# Adafruit_MagTag_2_9in_Rev_C1.net
KiCad netlist of a schematic drawn in EAGLE
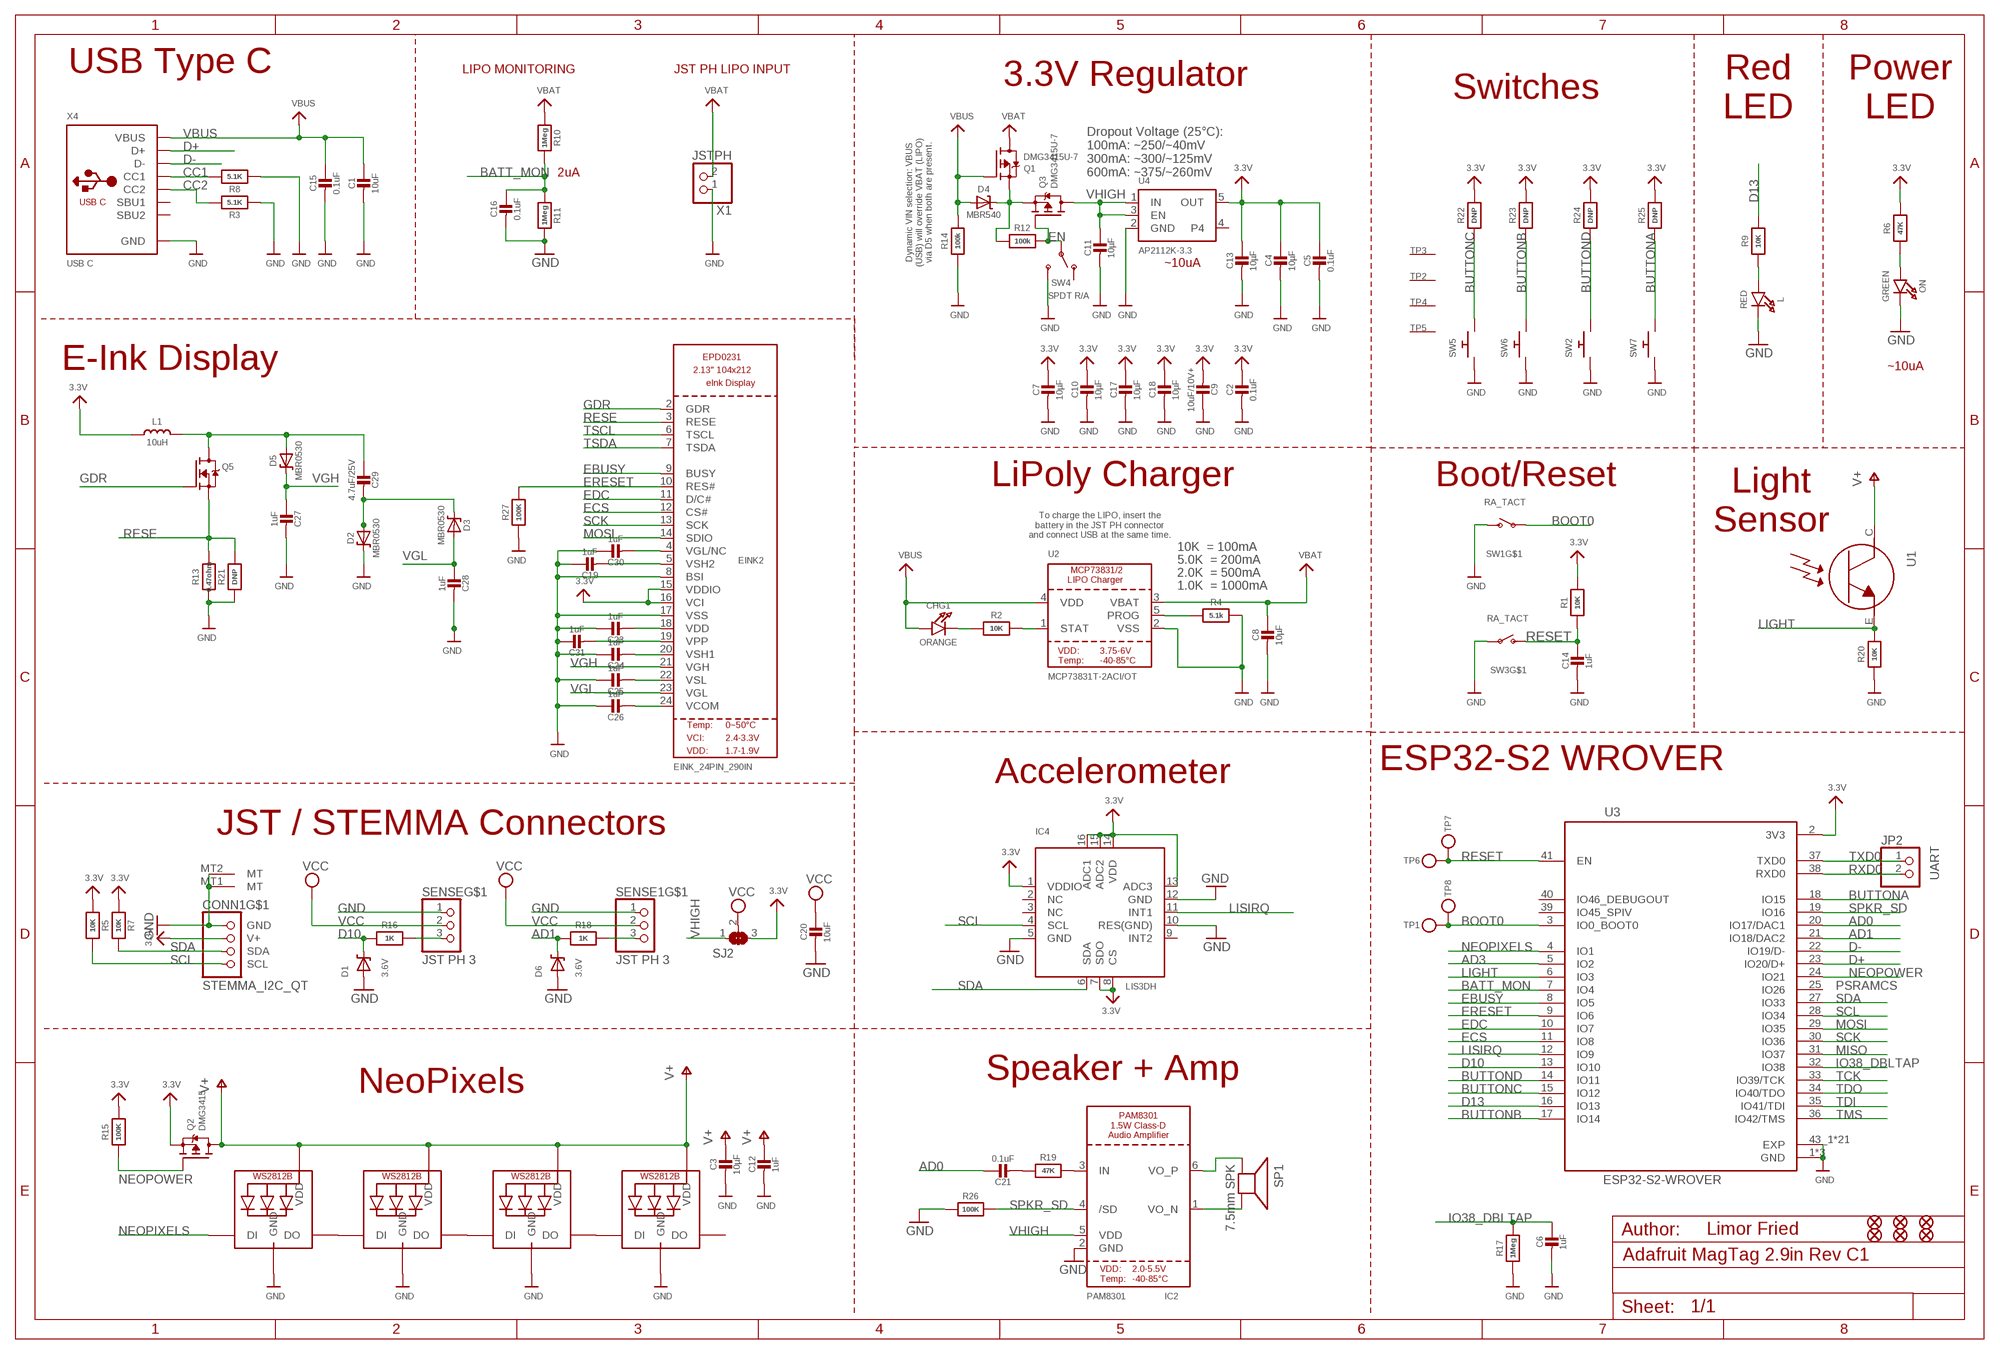
[diagram p0: schematic, sheet 1]

(export (version "E")
  (design (tool "Eeschema 10.0.6"))
  (components
    (comp (ref "C1")
      (value "10uF")
      (footprint "eagle-import:0805-NO")
      (libsource (lib "eagle-import") (part "CAP_CERAMIC0805-NOOUTLINE"))
    )
    (comp (ref "C2")
      (value "0.1uF")
      (footprint "eagle-import:0603-NO")
      (libsource (lib "eagle-import") (part "CAP_CERAMIC0603_NO"))
    )
    (comp (ref "C3")
      (value "10µF")
      (footprint "eagle-import:0805-NO")
      (libsource (lib "eagle-import") (part "CAP_CERAMIC0805-NOOUTLINE"))
    )
    (comp (ref "C4")
      (value "10µF")
      (footprint "eagle-import:0805-NO")
      (libsource (lib "eagle-import") (part "CAP_CERAMIC0805-NOOUTLINE"))
    )
    (comp (ref "C5")
      (value "0.1uF")
      (footprint "eagle-import:0603-NO")
      (libsource (lib "eagle-import") (part "CAP_CERAMIC0603_NO"))
    )
    (comp (ref "C6")
      (value "1uF")
      (footprint "eagle-import:0603-NO")
      (libsource (lib "eagle-import") (part "CAP_CERAMIC0603_NO"))
    )
    (comp (ref "C7")
      (value "10µF")
      (footprint "eagle-import:0805-NO")
      (libsource (lib "eagle-import") (part "CAP_CERAMIC0805-NOOUTLINE"))
    )
    (comp (ref "C8")
      (value "10µF")
      (footprint "eagle-import:0805-NO")
      (libsource (lib "eagle-import") (part "CAP_CERAMIC0805-NOOUTLINE"))
    )
    (comp (ref "C9")
      (value "10uF/10V+")
      (footprint "eagle-import:0805-NO")
      (libsource (lib "eagle-import") (part "CAP_CERAMIC0805-NOOUTLINE"))
    )
    (comp (ref "C10")
      (value "10µF")
      (footprint "eagle-import:0805-NO")
      (libsource (lib "eagle-import") (part "CAP_CERAMIC0805-NOOUTLINE"))
    )
    (comp (ref "C11")
      (value "10µF")
      (footprint "eagle-import:0805-NO")
      (libsource (lib "eagle-import") (part "CAP_CERAMIC0805-NOOUTLINE"))
    )
    (comp (ref "C12")
      (value "1uF")
      (footprint "eagle-import:0603-NO")
      (libsource (lib "eagle-import") (part "CAP_CERAMIC0603_NO"))
    )
    (comp (ref "C13")
      (value "10µF")
      (footprint "eagle-import:0805-NO")
      (libsource (lib "eagle-import") (part "CAP_CERAMIC0805-NOOUTLINE"))
    )
    (comp (ref "C14")
      (value "1uF")
      (footprint "eagle-import:0603-NO")
      (libsource (lib "eagle-import") (part "CAP_CERAMIC0603_NO"))
    )
    (comp (ref "C15")
      (value "0.1uF")
      (footprint "eagle-import:0603-NO")
      (libsource (lib "eagle-import") (part "CAP_CERAMIC0603_NO"))
    )
    (comp (ref "C16")
      (value "0.1uF")
      (footprint "eagle-import:0603-NO")
      (libsource (lib "eagle-import") (part "CAP_CERAMIC0603_NO"))
    )
    (comp (ref "C17")
      (value "10µF")
      (footprint "eagle-import:0805-NO")
      (libsource (lib "eagle-import") (part "CAP_CERAMIC0805-NOOUTLINE"))
    )
    (comp (ref "C18")
      (value "10µF")
      (footprint "eagle-import:0805-NO")
      (libsource (lib "eagle-import") (part "CAP_CERAMIC0805-NOOUTLINE"))
    )
    (comp (ref "C19")
      (value "1uF")
      (footprint "eagle-import:0805-NO")
      (libsource (lib "eagle-import") (part "CAP_CERAMIC0805-NOOUTLINE"))
    )
    (comp (ref "C20")
      (value "10uF")
      (footprint "eagle-import:0805-NO")
      (libsource (lib "eagle-import") (part "CAP_CERAMIC0805-NOOUTLINE"))
    )
    (comp (ref "C21")
      (value "0.1uF")
      (footprint "eagle-import:0603-NO")
      (libsource (lib "eagle-import") (part "CAP_CERAMIC0603_NO"))
    )
    (comp (ref "C23")
      (value "1uF")
      (footprint "eagle-import:0805-NO")
      (libsource (lib "eagle-import") (part "CAP_CERAMIC0805-NOOUTLINE"))
    )
    (comp (ref "C24")
      (value "1uF")
      (footprint "eagle-import:0805-NO")
      (libsource (lib "eagle-import") (part "CAP_CERAMIC0805-NOOUTLINE"))
    )
    (comp (ref "C25")
      (value "1uF")
      (footprint "eagle-import:0805-NO")
      (libsource (lib "eagle-import") (part "CAP_CERAMIC0805-NOOUTLINE"))
    )
    (comp (ref "C26")
      (value "1uF")
      (footprint "eagle-import:0805-NO")
      (libsource (lib "eagle-import") (part "CAP_CERAMIC0805-NOOUTLINE"))
    )
    (comp (ref "C27")
      (value "1uF")
      (footprint "eagle-import:0805-NO")
      (libsource (lib "eagle-import") (part "CAP_CERAMIC0805-NOOUTLINE"))
    )
    (comp (ref "C28")
      (value "1uF")
      (footprint "eagle-import:0805-NO")
      (libsource (lib "eagle-import") (part "CAP_CERAMIC0805-NOOUTLINE"))
    )
    (comp (ref "C29")
      (value "4.7uF/25V")
      (footprint "eagle-import:0805-NO")
      (libsource (lib "eagle-import") (part "CAP_CERAMIC0805-NOOUTLINE"))
    )
    (comp (ref "C30")
      (value "1uF")
      (footprint "eagle-import:0805-NO")
      (libsource (lib "eagle-import") (part "CAP_CERAMIC0805-NOOUTLINE"))
    )
    (comp (ref "C31")
      (value "1uF")
      (footprint "eagle-import:0805-NO")
      (libsource (lib "eagle-import") (part "CAP_CERAMIC0805-NOOUTLINE"))
    )
    (comp (ref "CHG1")
      (value "ORANGE")
      (footprint "eagle-import:CHIPLED_0603_NOOUTLINE")
      (libsource (lib "eagle-import") (part "LED0603_NOOUTLINE"))
    )
    (comp (ref "CONN1")
      (value "STEMMA_I2C_QT")
      (footprint "eagle-import:JST_SH4")
      (libsource (lib "eagle-import") (part "STEMMA_I2C_QT"))
    )
    (comp (ref "D1")
      (value "3.6V")
      (footprint "eagle-import:SOD-323")
      (libsource (lib "eagle-import") (part "DIODE-ZENERSOD323"))
    )
    (comp (ref "D2")
      (value "MBR0530")
      (footprint "eagle-import:SOD-123")
      (libsource (lib "eagle-import") (part "DIODE-SCHOTTKYSOD-123"))
    )
    (comp (ref "D3")
      (value "MBR0530")
      (footprint "eagle-import:SOD-123")
      (libsource (lib "eagle-import") (part "DIODE-SCHOTTKYSOD-123"))
    )
    (comp (ref "D4")
      (value "MBR540")
      (footprint "eagle-import:SOD-123")
      (libsource (lib "eagle-import") (part "DIODE-SCHOTTKYSOD-123"))
    )
    (comp (ref "D5")
      (value "MBR0530")
      (footprint "eagle-import:SOD-123")
      (libsource (lib "eagle-import") (part "DIODE-SCHOTTKYSOD-123"))
    )
    (comp (ref "D6")
      (value "3.6V")
      (footprint "eagle-import:SOD-323")
      (libsource (lib "eagle-import") (part "DIODE-ZENERSOD323"))
    )
    (comp (ref "EINK2")
      (value "EINK_24PIN_290IN")
      (footprint "eagle-import:EINK_290IN")
      (libsource (lib "eagle-import") (part "EINK_24PIN_290IN"))
    )
    (comp (ref "FID1")
      (value "FIDUCIAL_1MM")
      (footprint "eagle-import:FIDUCIAL_1MM")
      (libsource (lib "eagle-import") (part "FIDUCIAL_1MM"))
    )
    (comp (ref "FID2")
      (value "FIDUCIAL_1MM")
      (footprint "eagle-import:FIDUCIAL_1MM")
      (libsource (lib "eagle-import") (part "FIDUCIAL_1MM"))
    )
    (comp (ref "FID3")
      (value "FIDUCIAL_1MM")
      (footprint "eagle-import:FIDUCIAL_1MM")
      (libsource (lib "eagle-import") (part "FIDUCIAL_1MM"))
    )
    (comp (ref "FID4")
      (value "FIDUCIAL_1MM")
      (footprint "eagle-import:FIDUCIAL_1MM")
      (libsource (lib "eagle-import") (part "FIDUCIAL_1MM"))
    )
    (comp (ref "FID5")
      (value "FIDUCIAL_1MM")
      (footprint "eagle-import:FIDUCIAL_1MM")
      (libsource (lib "eagle-import") (part "FIDUCIAL_1MM"))
    )
    (comp (ref "FID6")
      (value "FIDUCIAL_1MM")
      (footprint "eagle-import:FIDUCIAL_1MM")
      (libsource (lib "eagle-import") (part "FIDUCIAL_1MM"))
    )
    (comp (ref "IC2")
      (value "PAM8301")
      (footprint "eagle-import:SOT23-6")
      (libsource (lib "eagle-import") (part "PAM8301"))
    )
    (comp (ref "IC4")
      (value "LIS3DH")
      (footprint "eagle-import:LGA16_3X3MM")
      (libsource (lib "eagle-import") (part "ACCEL_LIS3DHTR"))
    )
    (comp (ref "JP2")
      (value "UART")
      (footprint "eagle-import:1X02_ROUND")
      (libsource (lib "eagle-import") (part "HEADER-1X2ROUND"))
    )
    (comp (ref "L")
      (value "RED")
      (footprint "eagle-import:CHIPLED_0603_NOOUTLINE")
      (libsource (lib "eagle-import") (part "LED0603_NOOUTLINE"))
    )
    (comp (ref "L1")
      (value "10uH")
      (footprint "eagle-import:INDUCTOR_4X4MM_NR401")
      (libsource (lib "eagle-import") (part "INDUCTORNR401"))
    )
    (comp (ref "LED2")
      (value "WS2812B_4020")
      (footprint "eagle-import:WS2812B_4020")
      (libsource (lib "eagle-import") (part "WS2812B_4020"))
    )
    (comp (ref "LED3")
      (value "WS2812B_4020")
      (footprint "eagle-import:WS2812B_4020")
      (libsource (lib "eagle-import") (part "WS2812B_4020"))
    )
    (comp (ref "LED4")
      (value "WS2812B_4020")
      (footprint "eagle-import:WS2812B_4020")
      (libsource (lib "eagle-import") (part "WS2812B_4020"))
    )
    (comp (ref "LED5")
      (value "WS2812B_4020")
      (footprint "eagle-import:WS2812B_4020")
      (libsource (lib "eagle-import") (part "WS2812B_4020"))
    )
    (comp (ref "ON")
      (value "GREEN")
      (footprint "eagle-import:CHIPLED_0603_NOOUTLINE")
      (libsource (lib "eagle-import") (part "LED0603_NOOUTLINE"))
    )
    (comp (ref "Q1")
      (value "DMG3415U-7")
      (footprint "eagle-import:SOT23-R")
      (libsource (lib "eagle-import") (part "MOSFET-P"))
    )
    (comp (ref "Q2")
      (value "DMG3415")
      (footprint "eagle-import:SOT23-R")
      (libsource (lib "eagle-import") (part "MOSFET-P"))
    )
    (comp (ref "Q3")
      (value "DMG3415U-7")
      (footprint "eagle-import:SOT23-R")
      (libsource (lib "eagle-import") (part "MOSFET-P"))
    )
    (comp (ref "Q5")
      (value "IRLML0100")
      (footprint "eagle-import:SOT23-3")
      (libsource (lib "eagle-import") (part "IRLML2060TRPBF"))
    )
    (comp (ref "R1")
      (value "10K")
      (footprint "eagle-import:0603-NO")
      (libsource (lib "eagle-import") (part "RESISTOR_0603_NOOUT"))
    )
    (comp (ref "R2")
      (value "10K")
      (footprint "eagle-import:0603-NO")
      (libsource (lib "eagle-import") (part "RESISTOR_0603_NOOUT"))
    )
    (comp (ref "R3")
      (value "5.1K")
      (footprint "eagle-import:0603-NO")
      (libsource (lib "eagle-import") (part "RESISTOR_0603_NOOUT"))
    )
    (comp (ref "R4")
      (value "5.1k")
      (footprint "eagle-import:0603-NO")
      (libsource (lib "eagle-import") (part "RESISTOR_0603_NOOUT"))
    )
    (comp (ref "R5")
      (value "10K")
      (footprint "eagle-import:0603-NO")
      (libsource (lib "eagle-import") (part "RESISTOR_0603_NOOUT"))
    )
    (comp (ref "R6")
      (value "47K")
      (footprint "eagle-import:0603-NO")
      (libsource (lib "eagle-import") (part "RESISTOR_0603_NOOUT"))
    )
    (comp (ref "R7")
      (value "10K")
      (footprint "eagle-import:0603-NO")
      (libsource (lib "eagle-import") (part "RESISTOR_0603_NOOUT"))
    )
    (comp (ref "R8")
      (value "5.1K")
      (footprint "eagle-import:0603-NO")
      (libsource (lib "eagle-import") (part "RESISTOR_0603_NOOUT"))
    )
    (comp (ref "R9")
      (value "10K")
      (footprint "eagle-import:0603-NO")
      (libsource (lib "eagle-import") (part "RESISTOR_0603_NOOUT"))
    )
    (comp (ref "R10")
      (value "1Meg")
      (footprint "eagle-import:0603-NO")
      (libsource (lib "eagle-import") (part "RESISTOR_0603_NOOUT"))
    )
    (comp (ref "R11")
      (value "1Meg")
      (footprint "eagle-import:0603-NO")
      (libsource (lib "eagle-import") (part "RESISTOR_0603_NOOUT"))
    )
    (comp (ref "R12")
      (value "100k")
      (footprint "eagle-import:0603-NO")
      (libsource (lib "eagle-import") (part "RESISTOR_0603_NOOUT"))
    )
    (comp (ref "R13")
      (value "0.47ohm")
      (footprint "eagle-import:0805_10MGAP")
      (libsource (lib "eagle-import") (part "RESISTOR0805_10MGAP"))
    )
    (comp (ref "R14")
      (value "100k")
      (footprint "eagle-import:0603-NO")
      (libsource (lib "eagle-import") (part "RESISTOR_0603_NOOUT"))
    )
    (comp (ref "R15")
      (value "100K")
      (footprint "eagle-import:0603-NO")
      (libsource (lib "eagle-import") (part "RESISTOR_0603_NOOUT"))
    )
    (comp (ref "R16")
      (value "1K")
      (footprint "eagle-import:0603-NO")
      (libsource (lib "eagle-import") (part "RESISTOR_0603_NOOUT"))
    )
    (comp (ref "R17")
      (value "1Meg")
      (footprint "eagle-import:0603-NO")
      (libsource (lib "eagle-import") (part "RESISTOR_0603_NOOUT"))
    )
    (comp (ref "R18")
      (value "1K")
      (footprint "eagle-import:0603-NO")
      (libsource (lib "eagle-import") (part "RESISTOR_0603_NOOUT"))
    )
    (comp (ref "R19")
      (value "47K")
      (footprint "eagle-import:0603-NO")
      (libsource (lib "eagle-import") (part "RESISTOR_0603_NOOUT"))
    )
    (comp (ref "R20")
      (value "10K")
      (footprint "eagle-import:0603-NO")
      (libsource (lib "eagle-import") (part "RESISTOR_0603_NOOUT"))
    )
    (comp (ref "R21")
      (value "DNP")
      (footprint "eagle-import:0805_10MGAP")
      (libsource (lib "eagle-import") (part "RESISTOR0805_10MGAP"))
    )
    (comp (ref "R22")
      (value "DNP")
      (footprint "eagle-import:0603-NO")
      (libsource (lib "eagle-import") (part "RESISTOR_0603_NOOUT"))
    )
    (comp (ref "R23")
      (value "DNP")
      (footprint "eagle-import:0603-NO")
      (libsource (lib "eagle-import") (part "RESISTOR_0603_NOOUT"))
    )
    (comp (ref "R24")
      (value "DNP")
      (footprint "eagle-import:0603-NO")
      (libsource (lib "eagle-import") (part "RESISTOR_0603_NOOUT"))
    )
    (comp (ref "R25")
      (value "DNP")
      (footprint "eagle-import:0603-NO")
      (libsource (lib "eagle-import") (part "RESISTOR_0603_NOOUT"))
    )
    (comp (ref "R26")
      (value "100K")
      (footprint "eagle-import:0603-NO")
      (libsource (lib "eagle-import") (part "RESISTOR_0603_NOOUT"))
    )
    (comp (ref "R27")
      (value "100K")
      (footprint "eagle-import:0603-NO")
      (libsource (lib "eagle-import") (part "RESISTOR_0603_NOOUT"))
    )
    (comp (ref "SENSE")
      (value "JST PH 3")
      (footprint "eagle-import:JSTPH3")
      (libsource (lib "eagle-import") (part "CON_JST_PH_3PIN"))
    )
    (comp (ref "SENSE1")
      (value "JST PH 3")
      (footprint "eagle-import:JSTPH3")
      (libsource (lib "eagle-import") (part "CON_JST_PH_3PIN"))
    )
    (comp (ref "SJ2")
      (value "SOLDERJUMPER_2WAY")
      (footprint "eagle-import:SOLDERJUMPER_2WAY_OPEN_NOPASTE")
      (libsource (lib "eagle-import") (part "SOLDERJUMPER_2WAY"))
    )
    (comp (ref "SP1")
      (value "7.5mm SPK")
      (footprint "eagle-import:BUZZER_SMT_7.5MM")
      (libsource (lib "eagle-import") (part "SPEAKER_7.5MM"))
    )
    (comp (ref "SW1")
      (value "RA_TACT")
      (footprint "eagle-import:SPST_TACTILE_RA")
      (libsource (lib "eagle-import") (part "SWITCH_SPST_TACT_RA"))
    )
    (comp (ref "SW2")
      (value "SWITCH_PUSHBUTTON_3.5X6MM")
      (footprint "eagle-import:TACTILE_3X6MM")
      (libsource (lib "eagle-import") (part "SWITCH_PUSHBUTTON_3.5X6MM"))
    )
    (comp (ref "SW3")
      (value "RA_TACT")
      (footprint "eagle-import:SPST_TACTILE_RA")
      (libsource (lib "eagle-import") (part "SWITCH_SPST_TACT_RA"))
    )
    (comp (ref "SW4")
      (value "SPDT R/A")
      (footprint "eagle-import:SPDT_SMT_SSSS811101")
      (libsource (lib "eagle-import") (part "SWITCH_SPDT"))
    )
    (comp (ref "SW5")
      (value "SWITCH_PUSHBUTTON_3.5X6MM")
      (footprint "eagle-import:TACTILE_3X6MM")
      (libsource (lib "eagle-import") (part "SWITCH_PUSHBUTTON_3.5X6MM"))
    )
    (comp (ref "SW6")
      (value "SWITCH_PUSHBUTTON_3.5X6MM")
      (footprint "eagle-import:TACTILE_3X6MM")
      (libsource (lib "eagle-import") (part "SWITCH_PUSHBUTTON_3.5X6MM"))
    )
    (comp (ref "SW7")
      (value "SWITCH_PUSHBUTTON_3.5X6MM")
      (footprint "eagle-import:TACTILE_3X6MM")
      (libsource (lib "eagle-import") (part "SWITCH_PUSHBUTTON_3.5X6MM"))
    )
    (comp (ref "TP1")
      (value "TESTPOINTROUND1.5MMNO")
      (footprint "eagle-import:TESTPOINT_ROUND_1.5MM_NO")
      (libsource (lib "eagle-import") (part "TESTPOINTROUND1.5MMNO"))
    )
    (comp (ref "TP2")
      (value "SEWTAP_SMTNUTM3")
      (footprint "eagle-import:SMT_NUT_3MM")
      (libsource (lib "eagle-import") (part "SEWTAP_SMTNUTM3"))
    )
    (comp (ref "TP3")
      (value "SEWTAP_SMTNUTM3")
      (footprint "eagle-import:SMT_NUT_3MM")
      (libsource (lib "eagle-import") (part "SEWTAP_SMTNUTM3"))
    )
    (comp (ref "TP4")
      (value "SEWTAP_SMTNUTM3")
      (footprint "eagle-import:SMT_NUT_3MM")
      (libsource (lib "eagle-import") (part "SEWTAP_SMTNUTM3"))
    )
    (comp (ref "TP5")
      (value "SEWTAP_SMTNUTM3")
      (footprint "eagle-import:SMT_NUT_3MM")
      (libsource (lib "eagle-import") (part "SEWTAP_SMTNUTM3"))
    )
    (comp (ref "TP6")
      (value "TESTPOINTROUND1.5MMNO")
      (footprint "eagle-import:TESTPOINT_ROUND_1.5MM_NO")
      (libsource (lib "eagle-import") (part "TESTPOINTROUND1.5MMNO"))
    )
    (comp (ref "TP7")
      (value "TESTPOINTROUND1.5MMNO")
      (footprint "eagle-import:TESTPOINT_ROUND_1.5MM_NO")
      (libsource (lib "eagle-import") (part "TESTPOINTROUND1.5MMNO"))
    )
    (comp (ref "TP8")
      (value "TESTPOINTROUND1.5MMNO")
      (footprint "eagle-import:TESTPOINT_ROUND_1.5MM_NO")
      (libsource (lib "eagle-import") (part "TESTPOINTROUND1.5MMNO"))
    )
    (comp (ref "U1")
      (value "PHOTOTRANSISTOR_PT19-315C")
      (footprint "eagle-import:ALS-PT19-315C")
      (libsource (lib "eagle-import") (part "PHOTOTRANSISTOR_PT19-315C"))
    )
    (comp (ref "U2")
      (value "MCP73831T-2ACI/OT")
      (footprint "eagle-import:SOT23-5")
      (libsource (lib "eagle-import") (part "MCP73831/2"))
    )
    (comp (ref "U3")
      (value "ESP32-S2-WROVER")
      (footprint "eagle-import:MODULE_ESP32-S2-WROVER")
      (fields (field (name "MF") "Espressif Systems"))
      (libsource (lib "eagle-import") (part "ESP32-S2-WROVER"))
    )
    (comp (ref "U4")
      (value "AP2112K-3.3")
      (footprint "eagle-import:SOT23-5")
      (libsource (lib "eagle-import") (part "VREG_SOT23-5"))
    )
    (comp (ref "X1")
      (value "JSTPH")
      (footprint "eagle-import:JSTPH2_BATT")
      (libsource (lib "eagle-import") (part "CON_JST_PH_2PIN_BATT"))
    )
    (comp (ref "X4")
      (value "USB C")
      (footprint "eagle-import:USB_C_CUSB31-CFM2AX-01-X")
      (libsource (lib "eagle-import") (part "USB_C"))
    )
  )
  (nets
    (net (code "1") (name "/AD0") (class "Default")
      (node (ref "C21") (pin "1") (pinfunction "1_1") (pintype "passive"))
      (node (ref "U3") (pin "20") (pinfunction "IO17/DAC1_20") (pintype "bidirectional"))
    )
    (net (code "2") (name "/AD1") (class "Default")
      (node (ref "D6") (pin "C") (pinfunction "C_C") (pintype "passive"))
      (node (ref "R18") (pin "2") (pinfunction "2_2") (pintype "passive"))
      (node (ref "U3") (pin "21") (pinfunction "IO18/DAC2_21") (pintype "bidirectional"))
    )
    (net (code "3") (name "/AD3") (class "Default")
      (node (ref "U3") (pin "5") (pinfunction "IO2_5") (pintype "bidirectional"))
    )
    (net (code "4") (name "/BATT_MON") (class "Default")
      (node (ref "C16") (pin "1") (pinfunction "1_1") (pintype "passive"))
      (node (ref "R10") (pin "2") (pinfunction "2_2") (pintype "passive"))
      (node (ref "R11") (pin "1") (pinfunction "1_1") (pintype "passive"))
      (node (ref "U3") (pin "7") (pinfunction "IO4_7") (pintype "bidirectional"))
    )
    (net (code "5") (name "/BOOT0") (class "Default")
      (node (ref "SW1") (pin "1") (pinfunction "P_1") (pintype "passive"))
      (node (ref "TP1") (pin "P$1") (pinfunction "P$1_P$1") (pintype "bidirectional"))
      (node (ref "TP8") (pin "P$1") (pinfunction "P$1_P$1") (pintype "bidirectional"))
      (node (ref "U3") (pin "3") (pinfunction "IO0_BOOT0_3") (pintype "bidirectional"))
    )
    (net (code "6") (name "/BUTTONA") (class "Default")
      (node (ref "R25") (pin "1") (pinfunction "1_1") (pintype "passive"))
      (node (ref "SW7") (pin "P$2") (pinfunction "P$2_P$2") (pintype "passive"))
      (node (ref "U3") (pin "18") (pinfunction "IO15_18") (pintype "bidirectional"))
    )
    (net (code "7") (name "/BUTTONB") (class "Default")
      (node (ref "R23") (pin "1") (pinfunction "1_1") (pintype "passive"))
      (node (ref "SW6") (pin "P$2") (pinfunction "P$2_P$2") (pintype "passive"))
      (node (ref "U3") (pin "17") (pinfunction "IO14_17") (pintype "bidirectional"))
    )
    (net (code "8") (name "/BUTTONC") (class "Default")
      (node (ref "R22") (pin "1") (pinfunction "1_1") (pintype "passive"))
      (node (ref "SW5") (pin "P$2") (pinfunction "P$2_P$2") (pintype "passive"))
      (node (ref "U3") (pin "15") (pinfunction "IO12_15") (pintype "bidirectional"))
    )
    (net (code "9") (name "/BUTTOND") (class "Default")
      (node (ref "R24") (pin "1") (pinfunction "1_1") (pintype "passive"))
      (node (ref "SW2") (pin "P$2") (pinfunction "P$2_P$2") (pintype "passive"))
      (node (ref "U3") (pin "14") (pinfunction "IO11_14") (pintype "bidirectional"))
    )
    (net (code "10") (name "/CC1") (class "Default")
      (node (ref "R8") (pin "2") (pinfunction "2_2") (pintype "passive"))
      (node (ref "X4") (pin "A5") (pinfunction "CC1_A5") (pintype "bidirectional"))
    )
    (net (code "11") (name "/CC2") (class "Default")
      (node (ref "R3") (pin "2") (pinfunction "2_2") (pintype "passive"))
      (node (ref "X4") (pin "B5") (pinfunction "CC2_B5") (pintype "bidirectional"))
    )
    (net (code "12") (name "/D+") (class "Default")
      (node (ref "U3") (pin "23") (pinfunction "IO20/D+_23") (pintype "bidirectional"))
      (node (ref "X4") (pin "A6") (pinfunction "D+_A6") (pintype "bidirectional"))
      (node (ref "X4") (pin "B6") (pinfunction "D+_B6") (pintype "bidirectional"))
    )
    (net (code "13") (name "/D-") (class "Default")
      (node (ref "U3") (pin "22") (pinfunction "IO19/D-_22") (pintype "bidirectional"))
      (node (ref "X4") (pin "A7") (pinfunction "D-_A7") (pintype "bidirectional"))
      (node (ref "X4") (pin "B7") (pinfunction "D-_B7") (pintype "bidirectional"))
    )
    (net (code "14") (name "/D10") (class "Default")
      (node (ref "D1") (pin "C") (pinfunction "C_C") (pintype "passive"))
      (node (ref "R16") (pin "2") (pinfunction "2_2") (pintype "passive"))
      (node (ref "U3") (pin "13") (pinfunction "IO10_13") (pintype "bidirectional"))
    )
    (net (code "15") (name "/D13") (class "Default")
      (node (ref "R9") (pin "2") (pinfunction "2_2") (pintype "passive"))
      (node (ref "U3") (pin "16") (pinfunction "IO13_16") (pintype "bidirectional"))
    )
    (net (code "16") (name "/EBUSY") (class "Default")
      (node (ref "EINK2") (pin "9") (pinfunction "BUSY_9") (pintype "output"))
      (node (ref "U3") (pin "8") (pinfunction "IO5_8") (pintype "bidirectional"))
    )
    (net (code "17") (name "/ECS") (class "Default")
      (node (ref "EINK2") (pin "12") (pinfunction "CS#_12") (pintype "input"))
      (node (ref "U3") (pin "11") (pinfunction "IO8_11") (pintype "bidirectional"))
    )
    (net (code "18") (name "/EDC") (class "Default")
      (node (ref "EINK2") (pin "11") (pinfunction "D/C#_11") (pintype "input"))
      (node (ref "U3") (pin "10") (pinfunction "IO7_10") (pintype "bidirectional"))
    )
    (net (code "19") (name "/EN") (class "Default")
      (node (ref "Q3") (pin "1") (pinfunction "G_1") (pintype "passive"))
      (node (ref "R12") (pin "2") (pinfunction "2_2") (pintype "passive"))
      (node (ref "SW4") (pin "B") (pinfunction "P_B") (pintype "passive"))
    )
    (net (code "20") (name "/ERESET") (class "Default")
      (node (ref "EINK2") (pin "10") (pinfunction "RES#_10") (pintype "input"))
      (node (ref "R27") (pin "2") (pinfunction "2_2") (pintype "passive"))
      (node (ref "U3") (pin "9") (pinfunction "IO6_9") (pintype "bidirectional"))
    )
    (net (code "21") (name "/GDR") (class "Default")
      (node (ref "EINK2") (pin "2") (pinfunction "GDR_2") (pintype "output"))
      (node (ref "Q5") (pin "1") (pinfunction "G_1") (pintype "bidirectional"))
    )
    (net (code "22") (name "/IO38_DBLTAP") (class "Default")
      (node (ref "C6") (pin "1") (pinfunction "1_1") (pintype "passive"))
      (node (ref "R17") (pin "2") (pinfunction "2_2") (pintype "passive"))
      (node (ref "U3") (pin "32") (pinfunction "IO38_32") (pintype "bidirectional"))
    )
    (net (code "23") (name "/LIGHT") (class "Default")
      (node (ref "R20") (pin "2") (pinfunction "2_2") (pintype "passive"))
      (node (ref "U1") (pin "E") (pinfunction "E_E") (pintype "bidirectional"))
      (node (ref "U3") (pin "6") (pinfunction "IO3_6") (pintype "bidirectional"))
    )
    (net (code "24") (name "/LISIRQ") (class "Default")
      (node (ref "IC4") (pin "11") (pinfunction "INT1_11") (pintype "output"))
      (node (ref "U3") (pin "12") (pinfunction "IO9_12") (pintype "bidirectional"))
    )
    (net (code "25") (name "/MISO") (class "Default")
      (node (ref "U3") (pin "31") (pinfunction "IO37_31") (pintype "bidirectional"))
    )
    (net (code "26") (name "/MOSI") (class "Default")
      (node (ref "EINK2") (pin "14") (pinfunction "SDIO_14") (pintype "bidirectional"))
      (node (ref "U3") (pin "29") (pinfunction "IO35_29") (pintype "input"))
    )
    (net (code "27") (name "/NEOPIXELS") (class "Default")
      (node (ref "LED2") (pin "1") (pinfunction "DI_1") (pintype "input"))
      (node (ref "U3") (pin "4") (pinfunction "IO1_4") (pintype "bidirectional"))
    )
    (net (code "28") (name "/NEOPOWER") (class "Default")
      (node (ref "Q2") (pin "1") (pinfunction "G_1") (pintype "passive"))
      (node (ref "R15") (pin "1") (pinfunction "1_1") (pintype "passive"))
      (node (ref "U3") (pin "24") (pinfunction "IO21_24") (pintype "bidirectional"))
    )
    (net (code "29") (name "/RESE") (class "Default")
      (node (ref "EINK2") (pin "3") (pinfunction "RESE_3") (pintype "input"))
      (node (ref "Q5") (pin "2") (pinfunction "S_2") (pintype "bidirectional"))
      (node (ref "R13") (pin "1") (pinfunction "1_1") (pintype "passive"))
      (node (ref "R21") (pin "1") (pinfunction "1_1") (pintype "passive"))
    )
    (net (code "30") (name "/RESET") (class "Default")
      (node (ref "C14") (pin "1") (pinfunction "1_1") (pintype "passive"))
      (node (ref "R1") (pin "1") (pinfunction "1_1") (pintype "passive"))
      (node (ref "SW3") (pin "2") (pinfunction "S_2") (pintype "passive"))
      (node (ref "TP6") (pin "P$1") (pinfunction "P$1_P$1") (pintype "bidirectional"))
      (node (ref "TP7") (pin "P$1") (pinfunction "P$1_P$1") (pintype "bidirectional"))
      (node (ref "U3") (pin "41") (pinfunction "EN_41") (pintype "input"))
    )
    (net (code "31") (name "/RXD0") (class "Default")
      (node (ref "JP2") (pin "2") (pinfunction "2_2") (pintype "passive"))
      (node (ref "U3") (pin "38") (pinfunction "RXD0_38") (pintype "bidirectional"))
    )
    (net (code "32") (name "/SCK") (class "Default")
      (node (ref "EINK2") (pin "13") (pinfunction "SCK_13") (pintype "bidirectional"))
      (node (ref "U3") (pin "30") (pinfunction "IO36_30") (pintype "bidirectional"))
    )
    (net (code "33") (name "/SCL") (class "Default")
      (node (ref "CONN1") (pin "4") (pinfunction "SCL_4") (pintype "passive"))
      (node (ref "IC4") (pin "4") (pinfunction "SCL_4") (pintype "bidirectional"))
      (node (ref "R5") (pin "2") (pinfunction "2_2") (pintype "passive"))
      (node (ref "U3") (pin "28") (pinfunction "IO34_28") (pintype "input"))
    )
    (net (code "34") (name "/SDA") (class "Default")
      (node (ref "CONN1") (pin "3") (pinfunction "SDA_3") (pintype "passive"))
      (node (ref "IC4") (pin "6") (pinfunction "SDA_6") (pintype "bidirectional"))
      (node (ref "R7") (pin "2") (pinfunction "2_2") (pintype "passive"))
      (node (ref "U3") (pin "27") (pinfunction "IO33_27") (pintype "bidirectional"))
    )
    (net (code "35") (name "/SPKR_SD") (class "Default")
      (node (ref "IC2") (pin "4") (pinfunction "/SD_4") (pintype "input"))
      (node (ref "R26") (pin "2") (pinfunction "2_2") (pintype "passive"))
      (node (ref "U3") (pin "19") (pinfunction "IO16_19") (pintype "bidirectional"))
    )
    (net (code "36") (name "/TCK") (class "Default")
      (node (ref "U3") (pin "33") (pinfunction "IO39/TCK_33") (pintype "bidirectional"))
    )
    (net (code "37") (name "/TDI") (class "Default")
      (node (ref "U3") (pin "35") (pinfunction "IO41/TDI_35") (pintype "bidirectional"))
    )
    (net (code "38") (name "/TDO") (class "Default")
      (node (ref "U3") (pin "34") (pinfunction "IO40/TDO_34") (pintype "bidirectional"))
    )
    (net (code "39") (name "/TMS") (class "Default")
      (node (ref "U3") (pin "36") (pinfunction "IO42/TMS_36") (pintype "bidirectional"))
    )
    (net (code "40") (name "/TSCL") (class "Default")
      (node (ref "EINK2") (pin "6") (pinfunction "TSCL_6") (pintype "output"))
    )
    (net (code "41") (name "/TSDA") (class "Default")
      (node (ref "EINK2") (pin "7") (pinfunction "TSDA_7") (pintype "bidirectional"))
    )
    (net (code "42") (name "/TXD0") (class "Default")
      (node (ref "JP2") (pin "1") (pinfunction "1_1") (pintype "passive"))
      (node (ref "U3") (pin "37") (pinfunction "TXD0_37") (pintype "bidirectional"))
    )
    (net (code "43") (name "/VGH") (class "Default")
      (node (ref "C27") (pin "1") (pinfunction "1_1") (pintype "passive"))
      (node (ref "D5") (pin "C") (pinfunction "C_C") (pintype "passive"))
      (node (ref "EINK2") (pin "21") (pinfunction "VGH_21") (pintype "passive"))
    )
    (net (code "44") (name "/VGL") (class "Default")
      (node (ref "C28") (pin "1") (pinfunction "1_1") (pintype "passive"))
      (node (ref "D3") (pin "A") (pinfunction "A_A") (pintype "passive"))
      (node (ref "EINK2") (pin "23") (pinfunction "VGL_23") (pintype "passive"))
    )
    (net (code "45") (name "/VHIGH") (class "Default")
      (node (ref "C11") (pin "1") (pinfunction "1_1") (pintype "passive"))
      (node (ref "IC2") (pin "5") (pinfunction "VDD_5") (pintype "power_in"))
      (node (ref "Q3") (pin "3") (pinfunction "D_3") (pintype "passive"))
      (node (ref "SJ2") (pin "1") (pinfunction "1_1") (pintype "passive"))
      (node (ref "U4") (pin "1") (pinfunction "IN_1") (pintype "power_in"))
      (node (ref "U4") (pin "3") (pinfunction "EN_3") (pintype "input"))
    )
    (net (code "46") (name "3.3V") (class "Default")
      (node (ref "C10") (pin "1") (pinfunction "1_1") (pintype "passive"))
      (node (ref "C13") (pin "1") (pinfunction "1_1") (pintype "passive"))
      (node (ref "C17") (pin "1") (pinfunction "1_1") (pintype "passive"))
      (node (ref "C18") (pin "1") (pinfunction "1_1") (pintype "passive"))
      (node (ref "C2") (pin "1") (pinfunction "1_1") (pintype "passive"))
      (node (ref "C4") (pin "1") (pinfunction "1_1") (pintype "passive"))
      (node (ref "C5") (pin "1") (pinfunction "1_1") (pintype "passive"))
      (node (ref "C7") (pin "1") (pinfunction "1_1") (pintype "passive"))
      (node (ref "C9") (pin "2") (pinfunction "2_2") (pintype "passive"))
      (node (ref "CONN1") (pin "2") (pinfunction "V+_2") (pintype "passive"))
      (node (ref "EINK2") (pin "15") (pinfunction "VDDIO_15") (pintype "power_in"))
      (node (ref "EINK2") (pin "16") (pinfunction "VCI_16") (pintype "power_in"))
      (node (ref "IC4") (pin "1") (pinfunction "VDDIO_1") (pintype "power_in"))
      (node (ref "IC4") (pin "13") (pinfunction "ADC3_13") (pintype "input"))
      (node (ref "IC4") (pin "14") (pinfunction "VDD_14") (pintype "power_in"))
      (node (ref "IC4") (pin "15") (pinfunction "ADC2_15") (pintype "input"))
      (node (ref "IC4") (pin "16") (pinfunction "ADC1_16") (pintype "input"))
      (node (ref "IC4") (pin "7") (pinfunction "SDO_7") (pintype "bidirectional"))
      (node (ref "IC4") (pin "8") (pinfunction "CS_8") (pintype "input"))
      (node (ref "L1") (pin "P$2") (pinfunction "2_P$2") (pintype "passive"))
      (node (ref "Q2") (pin "2") (pinfunction "S_2") (pintype "passive"))
      (node (ref "R1") (pin "2") (pinfunction "2_2") (pintype "passive"))
      (node (ref "R15") (pin "2") (pinfunction "2_2") (pintype "passive"))
      (node (ref "R22") (pin "2") (pinfunction "2_2") (pintype "passive"))
      (node (ref "R23") (pin "2") (pinfunction "2_2") (pintype "passive"))
      (node (ref "R24") (pin "2") (pinfunction "2_2") (pintype "passive"))
      (node (ref "R25") (pin "2") (pinfunction "2_2") (pintype "passive"))
      (node (ref "R5") (pin "1") (pinfunction "1_1") (pintype "passive"))
      (node (ref "R6") (pin "2") (pinfunction "2_2") (pintype "passive"))
      (node (ref "R7") (pin "1") (pinfunction "1_1") (pintype "passive"))
      (node (ref "SJ2") (pin "3") (pinfunction "3_3") (pintype "passive"))
      (node (ref "U3") (pin "2") (pinfunction "3V3_2") (pintype "power_in"))
      (node (ref "U4") (pin "5") (pinfunction "OUT_5") (pintype "power_in"))
    )
    (net (code "47") (name "GND") (class "Default")
      (node (ref "C1") (pin "2") (pinfunction "2_2") (pintype "passive"))
      (node (ref "C10") (pin "2") (pinfunction "2_2") (pintype "passive"))
      (node (ref "C11") (pin "2") (pinfunction "2_2") (pintype "passive"))
      (node (ref "C12") (pin "2") (pinfunction "2_2") (pintype "passive"))
      (node (ref "C13") (pin "2") (pinfunction "2_2") (pintype "passive"))
      (node (ref "C14") (pin "2") (pinfunction "2_2") (pintype "passive"))
      (node (ref "C15") (pin "2") (pinfunction "2_2") (pintype "passive"))
      (node (ref "C16") (pin "2") (pinfunction "2_2") (pintype "passive"))
      (node (ref "C17") (pin "2") (pinfunction "2_2") (pintype "passive"))
      (node (ref "C18") (pin "2") (pinfunction "2_2") (pintype "passive"))
      (node (ref "C19") (pin "1") (pinfunction "1_1") (pintype "passive"))
      (node (ref "C2") (pin "2") (pinfunction "2_2") (pintype "passive"))
      (node (ref "C20") (pin "2") (pinfunction "2_2") (pintype "passive"))
      (node (ref "C23") (pin "1") (pinfunction "1_1") (pintype "passive"))
      (node (ref "C24") (pin "1") (pinfunction "1_1") (pintype "passive"))
      (node (ref "C25") (pin "1") (pinfunction "1_1") (pintype "passive"))
      (node (ref "C26") (pin "1") (pinfunction "1_1") (pintype "passive"))
      (node (ref "C27") (pin "2") (pinfunction "2_2") (pintype "passive"))
      (node (ref "C28") (pin "2") (pinfunction "2_2") (pintype "passive"))
      (node (ref "C3") (pin "2") (pinfunction "2_2") (pintype "passive"))
      (node (ref "C30") (pin "1") (pinfunction "1_1") (pintype "passive"))
      (node (ref "C31") (pin "1") (pinfunction "1_1") (pintype "passive"))
      (node (ref "C4") (pin "2") (pinfunction "2_2") (pintype "passive"))
      (node (ref "C5") (pin "2") (pinfunction "2_2") (pintype "passive"))
      (node (ref "C6") (pin "2") (pinfunction "2_2") (pintype "passive"))
      (node (ref "C7") (pin "2") (pinfunction "2_2") (pintype "passive"))
      (node (ref "C8") (pin "2") (pinfunction "2_2") (pintype "passive"))
      (node (ref "C9") (pin "1") (pinfunction "1_1") (pintype "passive"))
      (node (ref "CONN1") (pin "1") (pinfunction "GND_1") (pintype "passive"))
      (node (ref "CONN1") (pin "MT1") (pinfunction "MT_MT1") (pintype "bidirectional"))
      (node (ref "CONN1") (pin "MT2") (pinfunction "MT_MT2") (pintype "bidirectional"))
      (node (ref "D1") (pin "A") (pinfunction "A_A") (pintype "passive"))
      (node (ref "D2") (pin "C") (pinfunction "C_C") (pintype "passive"))
      (node (ref "D6") (pin "A") (pinfunction "A_A") (pintype "passive"))
      (node (ref "EINK2") (pin "17") (pinfunction "VSS_17") (pintype "power_in"))
      (node (ref "EINK2") (pin "8") (pinfunction "BSI_8") (pintype "input"))
      (node (ref "IC2") (pin "2") (pinfunction "GND_2") (pintype "power_in"))
      (node (ref "IC4") (pin "10") (pinfunction "RES(GND)_10") (pintype "bidirectional"))
      (node (ref "IC4") (pin "12") (pinfunction "GND_12") (pintype "power_in"))
      (node (ref "IC4") (pin "5") (pinfunction "GND_5") (pintype "power_in"))
      (node (ref "L") (pin "C") (pinfunction "C_C") (pintype "passive"))
      (node (ref "LED2") (pin "4") (pinfunction "GND_4") (pintype "power_in"))
      (node (ref "LED3") (pin "4") (pinfunction "GND_4") (pintype "power_in"))
      (node (ref "LED4") (pin "4") (pinfunction "GND_4") (pintype "power_in"))
      (node (ref "LED5") (pin "4") (pinfunction "GND_4") (pintype "power_in"))
      (node (ref "ON") (pin "C") (pinfunction "C_C") (pintype "passive"))
      (node (ref "R11") (pin "2") (pinfunction "2_2") (pintype "passive"))
      (node (ref "R13") (pin "2") (pinfunction "2_2") (pintype "passive"))
      (node (ref "R14") (pin "1") (pinfunction "1_1") (pintype "passive"))
      (node (ref "R17") (pin "1") (pinfunction "1_1") (pintype "passive"))
      (node (ref "R20") (pin "1") (pinfunction "1_1") (pintype "passive"))
      (node (ref "R21") (pin "2") (pinfunction "2_2") (pintype "passive"))
      (node (ref "R26") (pin "1") (pinfunction "1_1") (pintype "passive"))
      (node (ref "R27") (pin "1") (pinfunction "1_1") (pintype "passive"))
      (node (ref "R3") (pin "1") (pinfunction "1_1") (pintype "passive"))
      (node (ref "R4") (pin "2") (pinfunction "2_2") (pintype "passive"))
      (node (ref "R8") (pin "1") (pinfunction "1_1") (pintype "passive"))
      (node (ref "SENSE") (pin "1") (pinfunction "1_1") (pintype "passive"))
      (node (ref "SENSE1") (pin "1") (pinfunction "1_1") (pintype "passive"))
      (node (ref "SW1") (pin "2") (pinfunction "S_2") (pintype "passive"))
      (node (ref "SW2") (pin "P$1") (pinfunction "P$1_P$1") (pintype "passive"))
      (node (ref "SW3") (pin "1") (pinfunction "P_1") (pintype "passive"))
      (node (ref "SW4") (pin "C") (pinfunction "S_C") (pintype "passive"))
      (node (ref "SW5") (pin "P$1") (pinfunction "P$1_P$1") (pintype "passive"))
      (node (ref "SW6") (pin "P$1") (pinfunction "P$1_P$1") (pintype "passive"))
      (node (ref "SW7") (pin "P$1") (pinfunction "P$1_P$1") (pintype "passive"))
      (node (ref "U2") (pin "2") (pinfunction "VSS_2") (pintype "power_in"))
      (node (ref "U3") (pin "1") (pinfunction "GND_1") (pintype "power_in"))
      (node (ref "U3") (pin "26") (pinfunction "GND_26") (pintype "power_in"))
      (node (ref "U3") (pin "42") (pinfunction "GND_42") (pintype "power_in"))
      (node (ref "U3") (pin "43_1") (pinfunction "EXP_43_1") (pintype "power_in"))
      (node (ref "U3") (pin "43_10") (pinfunction "EXP_43_10") (pintype "power_in"))
      (node (ref "U3") (pin "43_11") (pinfunction "EXP_43_11") (pintype "power_in"))
      (node (ref "U3") (pin "43_12") (pinfunction "EXP_43_12") (pintype "power_in"))
      (node (ref "U3") (pin "43_13") (pinfunction "EXP_43_13") (pintype "power_in"))
      (node (ref "U3") (pin "43_14") (pinfunction "EXP_43_14") (pintype "power_in"))
      (node (ref "U3") (pin "43_15") (pinfunction "EXP_43_15") (pintype "power_in"))
      (node (ref "U3") (pin "43_16") (pinfunction "EXP_43_16") (pintype "power_in"))
      (node (ref "U3") (pin "43_17") (pinfunction "EXP_43_17") (pintype "power_in"))
      (node (ref "U3") (pin "43_18") (pinfunction "EXP_43_18") (pintype "power_in"))
      (node (ref "U3") (pin "43_19") (pinfunction "EXP_43_19") (pintype "power_in"))
      (node (ref "U3") (pin "43_2") (pinfunction "EXP_43_2") (pintype "power_in"))
      (node (ref "U3") (pin "43_20") (pinfunction "EXP_43_20") (pintype "power_in"))
      (node (ref "U3") (pin "43_21") (pinfunction "EXP_43_21") (pintype "power_in"))
      (node (ref "U3") (pin "43_3") (pinfunction "EXP_43_3") (pintype "power_in"))
      (node (ref "U3") (pin "43_4") (pinfunction "EXP_43_4") (pintype "power_in"))
      (node (ref "U3") (pin "43_5") (pinfunction "EXP_43_5") (pintype "power_in"))
      (node (ref "U3") (pin "43_6") (pinfunction "EXP_43_6") (pintype "power_in"))
      (node (ref "U3") (pin "43_7") (pinfunction "EXP_43_7") (pintype "power_in"))
      (node (ref "U3") (pin "43_8") (pinfunction "EXP_43_8") (pintype "power_in"))
      (node (ref "U3") (pin "43_9") (pinfunction "EXP_43_9") (pintype "power_in"))
      (node (ref "U4") (pin "2") (pinfunction "GND_2") (pintype "power_in"))
      (node (ref "X1") (pin "1") (pinfunction "1_1") (pintype "passive"))
      (node (ref "X4") (pin "A1B12") (pinfunction "GND_A1B12") (pintype "power_in"))
      (node (ref "X4") (pin "B1A12") (pinfunction "GND_B1A12") (pintype "power_in"))
    )
    (net (code "48") (name "Net-(C21-Pad2)") (class "Default")
      (node (ref "C21") (pin "2") (pinfunction "2_2") (pintype "passive"))
      (node (ref "R19") (pin "1") (pinfunction "1_1") (pintype "passive"))
    )
    (net (code "49") (name "Net-(C29-Pad2)") (class "Default")
      (node (ref "C29") (pin "2") (pinfunction "2_2") (pintype "passive"))
      (node (ref "D2") (pin "A") (pinfunction "A_A") (pintype "passive"))
      (node (ref "D3") (pin "C") (pinfunction "C_C") (pintype "passive"))
    )
    (net (code "50") (name "Net-(CHG1-PadC)") (class "Default")
      (node (ref "CHG1") (pin "C") (pinfunction "C_C") (pintype "passive"))
      (node (ref "R2") (pin "1") (pinfunction "1_1") (pintype "passive"))
    )
    (net (code "51") (name "Net-(EINK2-VCOM)") (class "Default")
      (node (ref "C26") (pin "2") (pinfunction "2_2") (pintype "passive"))
      (node (ref "EINK2") (pin "24") (pinfunction "VCOM_24") (pintype "passive"))
    )
    (net (code "52") (name "Net-(EINK2-VDD)") (class "Default")
      (node (ref "C23") (pin "2") (pinfunction "2_2") (pintype "passive"))
      (node (ref "EINK2") (pin "18") (pinfunction "VDD_18") (pintype "passive"))
    )
    (net (code "53") (name "Net-(EINK2-VGL{slash}NC)") (class "Default")
      (node (ref "C30") (pin "2") (pinfunction "2_2") (pintype "passive"))
      (node (ref "EINK2") (pin "4") (pinfunction "VGL/NC_4") (pintype "bidirectional"))
    )
    (net (code "54") (name "Net-(EINK2-VPP)") (class "Default")
      (node (ref "C31") (pin "2") (pinfunction "2_2") (pintype "passive"))
      (node (ref "EINK2") (pin "19") (pinfunction "VPP_19") (pintype "passive"))
    )
    (net (code "55") (name "Net-(EINK2-VSH1)") (class "Default")
      (node (ref "C24") (pin "2") (pinfunction "2_2") (pintype "passive"))
      (node (ref "EINK2") (pin "20") (pinfunction "VSH1_20") (pintype "passive"))
    )
    (net (code "56") (name "Net-(EINK2-VSH2)") (class "Default")
      (node (ref "C19") (pin "2") (pinfunction "2_2") (pintype "passive"))
      (node (ref "EINK2") (pin "5") (pinfunction "VSH2_5") (pintype "passive"))
    )
    (net (code "57") (name "Net-(EINK2-VSL)") (class "Default")
      (node (ref "C25") (pin "2") (pinfunction "2_2") (pintype "passive"))
      (node (ref "EINK2") (pin "22") (pinfunction "VSL_22") (pintype "passive"))
    )
    (net (code "58") (name "Net-(IC2-IN)") (class "Default")
      (node (ref "IC2") (pin "3") (pinfunction "IN_3") (pintype "input"))
      (node (ref "R19") (pin "2") (pinfunction "2_2") (pintype "passive"))
    )
    (net (code "59") (name "Net-(IC2-VO_N)") (class "Default")
      (node (ref "IC2") (pin "1") (pinfunction "VO_N_1") (pintype "output"))
      (node (ref "SP1") (pin "-") (pinfunction "-_-") (pintype "passive"))
    )
    (net (code "60") (name "Net-(IC2-VO_P)") (class "Default")
      (node (ref "IC2") (pin "6") (pinfunction "VO_P_6") (pintype "output"))
      (node (ref "SP1") (pin "+") (pinfunction "+_+") (pintype "passive"))
    )
    (net (code "61") (name "Net-(L-PadA)") (class "Default")
      (node (ref "L") (pin "A") (pinfunction "A_A") (pintype "passive"))
      (node (ref "R9") (pin "1") (pinfunction "1_1") (pintype "passive"))
    )
    (net (code "62") (name "Net-(L1-1)") (class "Default")
      (node (ref "C29") (pin "1") (pinfunction "1_1") (pintype "passive"))
      (node (ref "D5") (pin "A") (pinfunction "A_A") (pintype "passive"))
      (node (ref "L1") (pin "P$1") (pinfunction "1_P$1") (pintype "passive"))
      (node (ref "Q5") (pin "3") (pinfunction "D_3") (pintype "bidirectional"))
    )
    (net (code "63") (name "Net-(LED2-DO)") (class "Default")
      (node (ref "LED2") (pin "3") (pinfunction "DO_3") (pintype "output"))
      (node (ref "LED3") (pin "1") (pinfunction "DI_1") (pintype "input"))
    )
    (net (code "64") (name "Net-(LED3-DO)") (class "Default")
      (node (ref "LED3") (pin "3") (pinfunction "DO_3") (pintype "output"))
      (node (ref "LED4") (pin "1") (pinfunction "DI_1") (pintype "input"))
    )
    (net (code "65") (name "Net-(LED4-DO)") (class "Default")
      (node (ref "LED4") (pin "3") (pinfunction "DO_3") (pintype "output"))
      (node (ref "LED5") (pin "1") (pinfunction "DI_1") (pintype "input"))
    )
    (net (code "66") (name "Net-(ON-PadA)") (class "Default")
      (node (ref "ON") (pin "A") (pinfunction "A_A") (pintype "passive"))
      (node (ref "R6") (pin "1") (pinfunction "1_1") (pintype "passive"))
    )
    (net (code "67") (name "Net-(Q1-S)") (class "Default")
      (node (ref "D4") (pin "C") (pinfunction "C_C") (pintype "passive"))
      (node (ref "Q1") (pin "2") (pinfunction "S_2") (pintype "passive"))
      (node (ref "Q3") (pin "2") (pinfunction "S_2") (pintype "passive"))
      (node (ref "R12") (pin "1") (pinfunction "1_1") (pintype "passive"))
    )
    (net (code "68") (name "Net-(R16-Pad1)") (class "Default")
      (node (ref "R16") (pin "1") (pinfunction "1_1") (pintype "passive"))
      (node (ref "SENSE") (pin "3") (pinfunction "3_3") (pintype "passive"))
    )
    (net (code "69") (name "Net-(R18-Pad1)") (class "Default")
      (node (ref "R18") (pin "1") (pinfunction "1_1") (pintype "passive"))
      (node (ref "SENSE1") (pin "3") (pinfunction "3_3") (pintype "passive"))
    )
    (net (code "70") (name "Net-(U2-PROG)") (class "Default")
      (node (ref "R4") (pin "1") (pinfunction "1_1") (pintype "passive"))
      (node (ref "U2") (pin "5") (pinfunction "PROG_5") (pintype "input"))
    )
    (net (code "71") (name "Net-(U2-STAT)") (class "Default")
      (node (ref "R2") (pin "2") (pinfunction "2_2") (pintype "passive"))
      (node (ref "U2") (pin "1") (pinfunction "STAT_1") (pintype "output"))
    )
    (net (code "72") (name "V+") (class "Default")
      (node (ref "C12") (pin "1") (pinfunction "1_1") (pintype "passive"))
      (node (ref "C3") (pin "1") (pinfunction "1_1") (pintype "passive"))
      (node (ref "LED2") (pin "2") (pinfunction "VDD_2") (pintype "power_in"))
      (node (ref "LED3") (pin "2") (pinfunction "VDD_2") (pintype "power_in"))
      (node (ref "LED4") (pin "2") (pinfunction "VDD_2") (pintype "power_in"))
      (node (ref "LED5") (pin "2") (pinfunction "VDD_2") (pintype "power_in"))
      (node (ref "Q2") (pin "3") (pinfunction "D_3") (pintype "passive"))
      (node (ref "U1") (pin "C") (pinfunction "C_C") (pintype "bidirectional"))
    )
    (net (code "73") (name "VBAT") (class "Default")
      (node (ref "C8") (pin "1") (pinfunction "1_1") (pintype "passive"))
      (node (ref "Q1") (pin "3") (pinfunction "D_3") (pintype "passive"))
      (node (ref "R10") (pin "1") (pinfunction "1_1") (pintype "passive"))
      (node (ref "U2") (pin "3") (pinfunction "VBAT_3") (pintype "power_in"))
      (node (ref "X1") (pin "2") (pinfunction "2_2") (pintype "passive"))
    )
    (net (code "74") (name "VBUS") (class "Default")
      (node (ref "C1") (pin "1") (pinfunction "1_1") (pintype "passive"))
      (node (ref "C15") (pin "1") (pinfunction "1_1") (pintype "passive"))
      (node (ref "CHG1") (pin "A") (pinfunction "A_A") (pintype "passive"))
      (node (ref "D4") (pin "A") (pinfunction "A_A") (pintype "passive"))
      (node (ref "Q1") (pin "1") (pinfunction "G_1") (pintype "passive"))
      (node (ref "R14") (pin "2") (pinfunction "2_2") (pintype "passive"))
      (node (ref "U2") (pin "4") (pinfunction "VDD_4") (pintype "power_in"))
      (node (ref "X4") (pin "A4B9") (pinfunction "VBUS_A4B9") (pintype "power_in"))
      (node (ref "X4") (pin "B4A9") (pinfunction "VBUS_B4A9") (pintype "power_in"))
    )
    (net (code "75") (name "VCC") (class "Default")
      (node (ref "C20") (pin "1") (pinfunction "1_1") (pintype "passive"))
      (node (ref "SENSE") (pin "2") (pinfunction "2_2") (pintype "passive"))
      (node (ref "SENSE1") (pin "2") (pinfunction "2_2") (pintype "passive"))
      (node (ref "SJ2") (pin "2") (pinfunction "2_2") (pintype "passive"))
    )
    (net (code "76") (name "unconnected-(IC4-INT2-Pad9)") (class "Default")
      (node (ref "IC4") (pin "9") (pinfunction "INT2_9") (pintype "output"))
    )
    (net (code "77") (name "unconnected-(IC4-NC-Pad2)") (class "Default")
      (node (ref "IC4") (pin "2") (pinfunction "NC_2") (pintype "no_connect"))
    )
    (net (code "78") (name "unconnected-(IC4-NC-Pad3)") (class "Default")
      (node (ref "IC4") (pin "3") (pinfunction "NC_3") (pintype "no_connect"))
    )
    (net (code "79") (name "unconnected-(LED5-DO-Pad3)") (class "Default")
      (node (ref "LED5") (pin "3") (pinfunction "DO_3") (pintype "output"))
    )
    (net (code "80") (name "unconnected-(SW4-O-PadA)") (class "Default")
      (node (ref "SW4") (pin "A") (pinfunction "O_A") (pintype "passive"))
    )
    (net (code "81") (name "unconnected-(TP2-SEW-PadP$1)") (class "Default")
      (node (ref "TP2") (pin "P$1") (pinfunction "SEW_P$1") (pintype "bidirectional"))
    )
    (net (code "82") (name "unconnected-(TP3-SEW-PadP$1)") (class "Default")
      (node (ref "TP3") (pin "P$1") (pinfunction "SEW_P$1") (pintype "bidirectional"))
    )
    (net (code "83") (name "unconnected-(TP4-SEW-PadP$1)") (class "Default")
      (node (ref "TP4") (pin "P$1") (pinfunction "SEW_P$1") (pintype "bidirectional"))
    )
    (net (code "84") (name "unconnected-(TP5-SEW-PadP$1)") (class "Default")
      (node (ref "TP5") (pin "P$1") (pinfunction "SEW_P$1") (pintype "bidirectional"))
    )
    (net (code "85") (name "unconnected-(U3-IO26-Pad25)") (class "Default")
      (node (ref "U3") (pin "25") (pinfunction "IO26_25") (pintype "bidirectional"))
    )
    (net (code "86") (name "unconnected-(U3-IO45_SPIV-Pad39)") (class "Default")
      (node (ref "U3") (pin "39") (pinfunction "IO45_SPIV_39") (pintype "bidirectional"))
    )
    (net (code "87") (name "unconnected-(U3-IO46_DEBUGOUT-Pad40)") (class "Default")
      (node (ref "U3") (pin "40") (pinfunction "IO46_DEBUGOUT_40") (pintype "input"))
    )
    (net (code "88") (name "unconnected-(U4-P4-Pad4)") (class "Default")
      (node (ref "U4") (pin "4") (pinfunction "P4_4") (pintype "bidirectional"))
    )
    (net (code "89") (name "unconnected-(X4-SBU1-PadA8)") (class "Default")
      (node (ref "X4") (pin "A8") (pinfunction "SBU1_A8") (pintype "bidirectional"))
    )
    (net (code "90") (name "unconnected-(X4-SBU2-PadB8)") (class "Default")
      (node (ref "X4") (pin "B8") (pinfunction "SBU2_B8") (pintype "bidirectional"))
    )
  )
)
